# Relay4_Block.net
KiCad netlist of a schematic drawn in Altium Designer
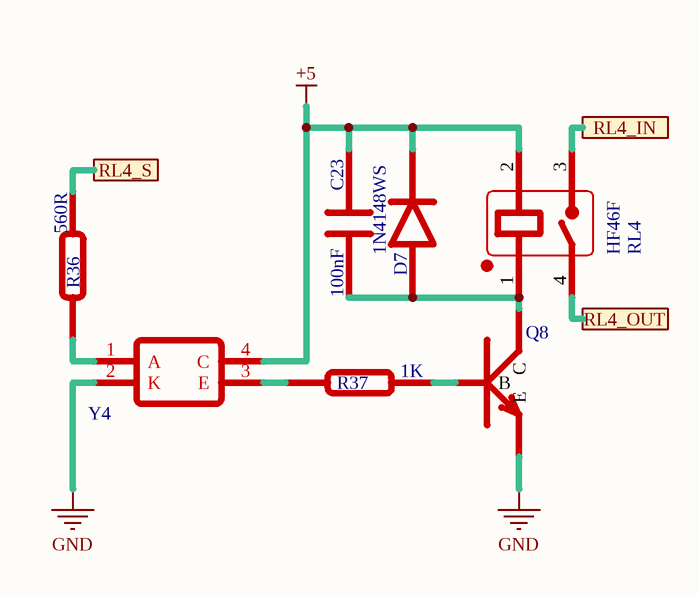
[diagram p0: Relay4_Block.SchDoc]

(export (version "E")
  (design (tool "Eeschema 10.0.6"))
  (components
    (comp (ref "C23")
      (value "100nF")
      (footprint "C0805")
      (description "Ceramic Capacitor")
      (libsource (lib "CTAI-Library") (part "CAP-CER"))
    )
    (comp (ref "D7")
      (value "1N4148WS")
      (footprint "SMA")
      (description "Small Signal Diode")
      (libsource (lib "CTAI-Library") (part "1N4148WS"))
    )
    (comp (ref "Q8")
      (value "S8050")
      (footprint "SOT-23")
      (description "NPN Transistors 0.5A Collector to Emitter 25V")
      (libsource (lib "CTAI-Library") (part "S8050"))
    )
    (comp (ref "R36")
      (value "560R")
      (footprint "R0603")
      (description "Resistor")
      (libsource (lib "CTAI-Library") (part "Resistor"))
    )
    (comp (ref "R37")
      (value "1K")
      (footprint "R0603")
      (description "Resistor")
      (libsource (lib "CTAI-Library") (part "Resistor"))
    )
    (comp (ref "RL4")
      (value "HF46F")
      (footprint "HF-46-X")
      (description "Relay 4 Pin")
      (libsource (lib "CTAI-Library") (part "HF46F"))
    )
    (comp (ref "Y4")
      (value "PHOTOCOUPLER")
      (footprint "SOP-4")
      (description "Photo-Coupler")
      (libsource (lib "CTAI-Library") (part "PC817"))
    )
  )
  (nets
    (net (code "1") (name "+5") (class "Default")
      (node (ref "C23") (pin "2") (pintype "passive"))
      (node (ref "D7") (pin "K") (pinfunction "K_K") (pintype "passive"))
      (node (ref "RL4") (pin "2") (pinfunction "2_2") (pintype "passive"))
      (node (ref "Y4") (pin "4") (pinfunction "C_4") (pintype "passive"))
    )
    (net (code "2") (name "/RL4_IN") (class "Default")
      (node (ref "RL4") (pin "3") (pinfunction "3_3") (pintype "passive"))
    )
    (net (code "3") (name "/RL4_OUT") (class "Default")
      (node (ref "RL4") (pin "4") (pinfunction "4_4") (pintype "passive"))
    )
    (net (code "4") (name "/RL4_S") (class "Default")
      (node (ref "R36") (pin "1") (pinfunction "1_1") (pintype "passive"))
    )
    (net (code "5") (name "GND") (class "Default")
      (node (ref "Q8") (pin "2") (pinfunction "E_2") (pintype "passive"))
      (node (ref "Y4") (pin "2") (pinfunction "K_2") (pintype "passive"))
    )
    (net (code "6") (name "Net-(Q8-B)") (class "Default")
      (node (ref "Q8") (pin "1") (pinfunction "B_1") (pintype "passive"))
      (node (ref "R37") (pin "1") (pinfunction "1_1") (pintype "passive"))
    )
    (net (code "7") (name "Net-(Q8-C)") (class "Default")
      (node (ref "C23") (pin "1") (pintype "passive"))
      (node (ref "D7") (pin "A") (pinfunction "A_A") (pintype "passive"))
      (node (ref "Q8") (pin "3") (pinfunction "C_3") (pintype "passive"))
      (node (ref "RL4") (pin "1") (pinfunction "1_1") (pintype "passive"))
    )
    (net (code "8") (name "Net-(Y4-A)") (class "Default")
      (node (ref "R36") (pin "2") (pinfunction "2_2") (pintype "passive"))
      (node (ref "Y4") (pin "1") (pinfunction "A_1") (pintype "passive"))
    )
    (net (code "9") (name "Net-(Y4-E)") (class "Default")
      (node (ref "R37") (pin "2") (pinfunction "2_2") (pintype "passive"))
      (node (ref "Y4") (pin "3") (pinfunction "E_3") (pintype "passive"))
    )
  )
)
